# Power_Stage.net
KiCad netlist of a schematic drawn in Altium Designer
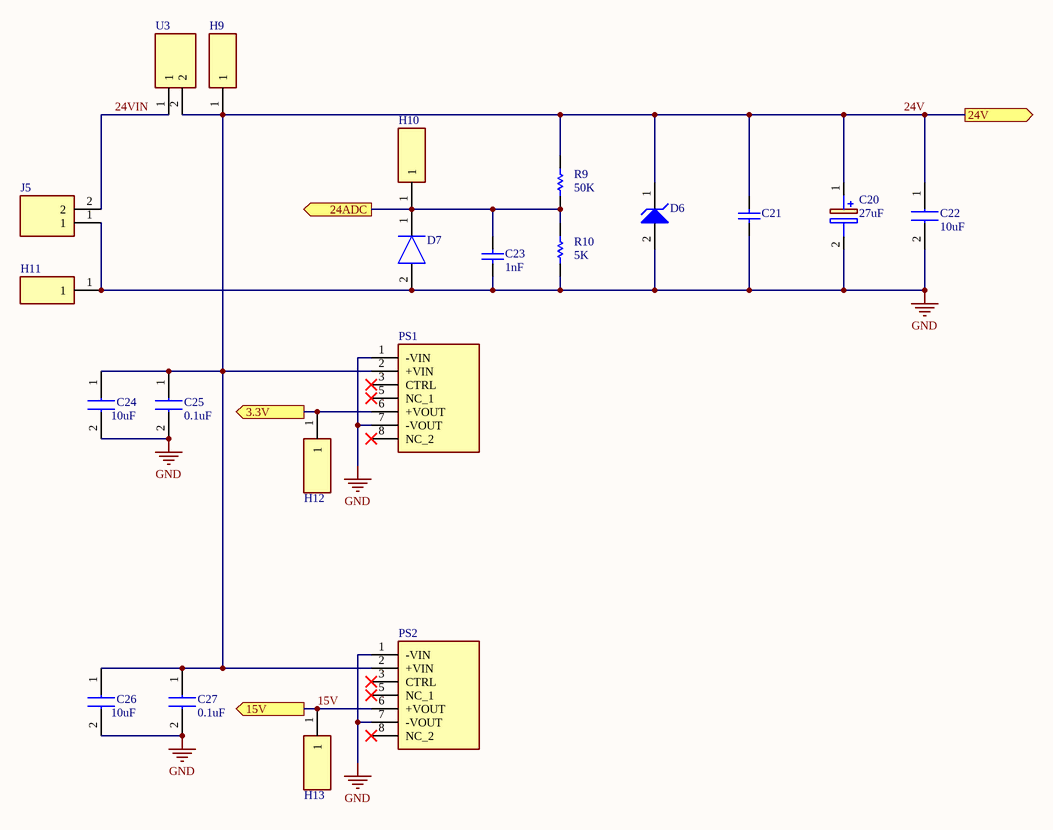
[diagram p0: Power_Stage.SchDoc]

(export (version "E")
  (design (tool "Eeschema 10.0.6"))
  (components
    (comp (ref "C20")
      (value "27uF")
      (footprint "ee_453_Schulz:CAPPRD200W55D500H1250")
      (description "50V 27uF electrolytic cap EEU-FS1H270B")
      (fields
        (field (name "MANUFACTURER_PART_NUMBER") "EEU-FS1H270B")
        (field (name "MOUSER PART NUMBER") "667-EEU-FS1H270B")
      )
      (libsource (lib "ee_453_Schulz") (part "EEU-FS1H270B"))
    )
    (comp (ref "C21")
      (value "VC060326A580RP")
      (footprint "CAPC1608X90X35ML15T15")
      (fields (field (name "MANUFACTURER") "AVX Interconnect / Elco"))
      (libsource (lib "Altium Content Vault") (part "CAP"))
    )
    (comp (ref "C22")
      (value "10uF")
      (footprint "MKS4B051004J00KSSD")
      (description "MKS4B051004J00KSSD")
      (fields (field (name "MOUSER PART NUMBER") "505-MKS410/50/10"))
      (libsource (lib "ee_453_Schulz") (part "MKS4B051004J00KSSD"))
    )
    (comp (ref "C23")
      (value "1nF")
      (footprint "CAPC2013X95X45NL10T25")
      (fields (field (name "PART NUMBER") "GRM2195C2A102JA01D") (field (name "MANUFACTURER") "Murata"))
      (libsource (lib "Altium Content Vault") (part "CAP"))
    )
    (comp (ref "C24")
      (value "10uF")
      (footprint "MKS4B051004J00KSSD")
      (description "Capacitor 50V")
      (fields
        (field (name "MANUFACTURER_PART_NUMBER") "MKS4B051004J00KSSD")
        (field (name "MOUSER PART NUMBER") "505-MKS410/50/10")
      )
      (libsource (lib "ee_453_Schulz") (part "MKS4B051004J00KSSD"))
    )
    (comp (ref "C25")
      (value "0.1uF")
      (footprint "K104K10X7RF5UH5")
      (description "Capacitor 50V")
      (fields
        (field (name "MANUFACTURER_PART_NUMBER") "K104K10X7RF5UH5")
        (field (name "MOUSER PART NUMBER") "594-K104K10X7RF5UH5")
      )
      (libsource (lib "ee_453_Schulz") (part "K104K10X7RF5UH5"))
    )
    (comp (ref "C26")
      (value "10uF")
      (footprint "MKS4B051004J00KSSD")
      (description "Capacitor 50V")
      (fields
        (field (name "MANUFACTURER_PART_NUMBER") "MKS4B051004J00KSSD")
        (field (name "MOUSER PART NUMBER") "505-MKS410/50/10")
      )
      (libsource (lib "ee_453_Schulz") (part "MKS4B051004J00KSSD"))
    )
    (comp (ref "C27")
      (value "0.1uF")
      (footprint "K104K10X7RF5UH5")
      (description "Capacitor 50V")
      (fields
        (field (name "MANUFACTURER_PART_NUMBER") "K104K10X7RF5UH5")
        (field (name "MOUSER PART NUMBER") "594-K104K10X7RF5UH5")
      )
      (libsource (lib "ee_453_Schulz") (part "K104K10X7RF5UH5"))
    )
    (comp (ref "D6")
      (value "P6KE47A")
      (footprint "ONSC-SURMETIC40-2-017AA-01")
      (fields (field (name "PARTNUMBER") "P6KE47AG") (field (name "MANUFACTURER") "On Semiconductor"))
      (libsource (lib "Altium Content Vault") (part "ONSC-K1A2-2"))
    )
    (comp (ref "D7")
      (value "BZX584C3V3-G3-08")
      (footprint "SODFL1608X75N")
      (description "Diode")
      (fields (field (name "MOUSER PART NUMBER") "78-BZX584C3V3-G3-08"))
      (libsource (lib "ee_453_Schulz") (part "BZX584C3V3-G3-08"))
    )
    (comp (ref "H9")
      (value "5003")
      (footprint "5003")
      (description "Hardware")
      (fields (field (name "MOUSER PART NUMBER") "534-5003"))
      (libsource (lib "") (part "5003_2"))
    )
    (comp (ref "H10")
      (value "5003")
      (footprint "5003")
      (description "Hardware")
      (fields (field (name "MOUSER PART NUMBER") "534-5003"))
      (libsource (lib "") (part "5003_2"))
    )
    (comp (ref "H11")
      (value "5003")
      (footprint "5003")
      (description "Hardware")
      (fields (field (name "MOUSER PART NUMBER") "534-5003"))
      (libsource (lib "ee_453_Schulz") (part "5003"))
    )
    (comp (ref "H12")
      (value "5003")
      (footprint "5003")
      (description "Hardware")
      (fields (field (name "MOUSER PART NUMBER") "534-5003"))
      (libsource (lib "") (part "5003_1"))
    )
    (comp (ref "H13")
      (value "5003")
      (footprint "5003")
      (description "Hardware")
      (fields (field (name "MOUSER PART NUMBER") "534-5003"))
      (libsource (lib "") (part "5003_1"))
    )
    (comp (ref "J5")
      (value "1985881")
      (footprint "SHDR2W110P0X500_1X2_1000X985X1390P")
      (description "2-Port Connector")
      (fields (field (name "MOUSER PART NUMBER") "651-1985881") (field (name "RS PART NUMBER") "4670338"))
      (libsource (lib "ee_453_Schulz") (part "1985881"))
    )
    (comp (ref "PS1")
      (value "RS3-243.3S")
      (footprint "RS32433S")
      (description "Power Supply")
      (fields (field (name "MOUSER PART NUMBER") "919-RS3-243.3S") (field (name "RS PART NUMBER") "0163748P"))
      (libsource (lib "ee_453_Schulz") (part "RS3-243.3S"))
    )
    (comp (ref "PS2")
      (value "RS3-2415S")
      (footprint "RS32415S")
      (description "Power Supply")
      (fields (field (name "MOUSER PART NUMBER") "919-RS3-2415S"))
      (libsource (lib "ee_453_Schulz") (part "RS3-2415S"))
    )
    (comp (ref "R9")
      (value "50K")
      (footprint "AXIAL-0.3")
      (description "Resistor")
      (fields (field (name "Comment") "Res1") (field (name "PUBLISHER") "Altium Limited"))
      (libsource (lib "Miscellaneous Devices") (part "Res1"))
    )
    (comp (ref "R10")
      (value "5K")
      (footprint "AXIAL-0.3")
      (description "Resistor")
      (fields (field (name "Comment") "Res1") (field (name "PUBLISHER") "Altium Limited"))
      (libsource (lib "Miscellaneous Devices") (part "Res1"))
    )
    (comp (ref "U3")
      (value "0PTF0078P")
      (footprint "0PTF0078P")
      (description "Fuse holder")
      (fields (field (name "MOUSER PART NUMBER") "576-0PTF0078P") (field (name "RS PART NUMBER") "1740656"))
      (libsource (lib "ee_453_Schulz") (part "0PTF0078P"))
    )
  )
  (nets
    (net (code "1") (name "/3.3V") (class "Default")
      (node (ref "H12") (pin "1") (pinfunction "1_1") (pintype "passive"))
      (node (ref "PS1") (pin "6") (pinfunction "+VOUT_6") (pintype "passive"))
    )
    (net (code "2") (name "/15V") (class "Default")
      (node (ref "H13") (pin "1") (pinfunction "1_1") (pintype "passive"))
      (node (ref "PS2") (pin "6") (pinfunction "+VOUT_6") (pintype "passive"))
    )
    (net (code "3") (name "/24ADC") (class "Default")
      (node (ref "C23") (pin "2") (pinfunction "2_2") (pintype "passive"))
      (node (ref "D7") (pin "1") (pinfunction "K_1") (pintype "passive"))
      (node (ref "H10") (pin "1") (pinfunction "1_1") (pintype "passive"))
      (node (ref "R10") (pin "2") (pinfunction "2_2") (pintype "passive"))
      (node (ref "R9") (pin "1") (pinfunction "1_1") (pintype "passive"))
    )
    (net (code "4") (name "/24V") (class "Default")
      (node (ref "C20") (pin "1") (pinfunction "+_1") (pintype "passive"))
      (node (ref "C21") (pin "2") (pinfunction "2_2") (pintype "passive"))
      (node (ref "C22") (pin "1") (pinfunction "1_1") (pintype "passive"))
      (node (ref "C24") (pin "1") (pinfunction "1_1") (pintype "passive"))
      (node (ref "C25") (pin "1") (pinfunction "1_1") (pintype "passive"))
      (node (ref "C26") (pin "1") (pinfunction "1_1") (pintype "passive"))
      (node (ref "C27") (pin "1") (pinfunction "1_1") (pintype "passive"))
      (node (ref "D6") (pin "1") (pinfunction "K_1") (pintype "passive"))
      (node (ref "H9") (pin "1") (pinfunction "1_1") (pintype "passive"))
      (node (ref "PS1") (pin "2") (pinfunction "+VIN_2") (pintype "passive"))
      (node (ref "PS2") (pin "2") (pinfunction "+VIN_2") (pintype "passive"))
      (node (ref "R9") (pin "2") (pinfunction "2_2") (pintype "passive"))
      (node (ref "U3") (pin "2") (pinfunction "2_2") (pintype "passive"))
    )
    (net (code "5") (name "/24VIN") (class "Default")
      (node (ref "J5") (pin "2") (pinfunction "2_2") (pintype "passive"))
      (node (ref "U3") (pin "1") (pinfunction "1_1") (pintype "passive"))
    )
    (net (code "6") (name "GND") (class "Default")
      (node (ref "C20") (pin "2") (pinfunction "-_2") (pintype "passive"))
      (node (ref "C21") (pin "1") (pinfunction "1_1") (pintype "passive"))
      (node (ref "C22") (pin "2") (pinfunction "2_2") (pintype "passive"))
      (node (ref "C23") (pin "1") (pinfunction "1_1") (pintype "passive"))
      (node (ref "C24") (pin "2") (pinfunction "2_2") (pintype "passive"))
      (node (ref "C25") (pin "2") (pinfunction "2_2") (pintype "passive"))
      (node (ref "C26") (pin "2") (pinfunction "2_2") (pintype "passive"))
      (node (ref "C27") (pin "2") (pinfunction "2_2") (pintype "passive"))
      (node (ref "D6") (pin "2") (pinfunction "A_2") (pintype "passive"))
      (node (ref "D7") (pin "2") (pinfunction "A_2") (pintype "passive"))
      (node (ref "H11") (pin "1") (pinfunction "1_1") (pintype "passive"))
      (node (ref "J5") (pin "1") (pinfunction "1_1") (pintype "passive"))
      (node (ref "PS1") (pin "1") (pinfunction "-VIN_1") (pintype "passive"))
      (node (ref "PS1") (pin "7") (pinfunction "-VOUT_7") (pintype "passive"))
      (node (ref "PS2") (pin "1") (pinfunction "-VIN_1") (pintype "passive"))
      (node (ref "PS2") (pin "7") (pinfunction "-VOUT_7") (pintype "passive"))
      (node (ref "R10") (pin "1") (pinfunction "1_1") (pintype "passive"))
    )
    (net (code "7") (name "unconnected-(PS1-CTRL-Pad3)") (class "Default")
      (node (ref "PS1") (pin "3") (pinfunction "CTRL_3") (pintype "passive+no_connect"))
    )
    (net (code "8") (name "unconnected-(PS1-NC_1-Pad5)") (class "Default")
      (node (ref "PS1") (pin "5") (pinfunction "NC_1_5") (pintype "passive+no_connect"))
    )
    (net (code "9") (name "unconnected-(PS1-NC_2-Pad8)") (class "Default")
      (node (ref "PS1") (pin "8") (pinfunction "NC_2_8") (pintype "passive+no_connect"))
    )
    (net (code "10") (name "unconnected-(PS2-CTRL-Pad3)") (class "Default")
      (node (ref "PS2") (pin "3") (pinfunction "CTRL_3") (pintype "passive+no_connect"))
    )
    (net (code "11") (name "unconnected-(PS2-NC_1-Pad5)") (class "Default")
      (node (ref "PS2") (pin "5") (pinfunction "NC_1_5") (pintype "passive+no_connect"))
    )
    (net (code "12") (name "unconnected-(PS2-NC_2-Pad8)") (class "Default")
      (node (ref "PS2") (pin "8") (pinfunction "NC_2_8") (pintype "passive+no_connect"))
    )
  )
)
